# 24V_Load_Switches.net
KiCad netlist of a schematic drawn in Altium Designer
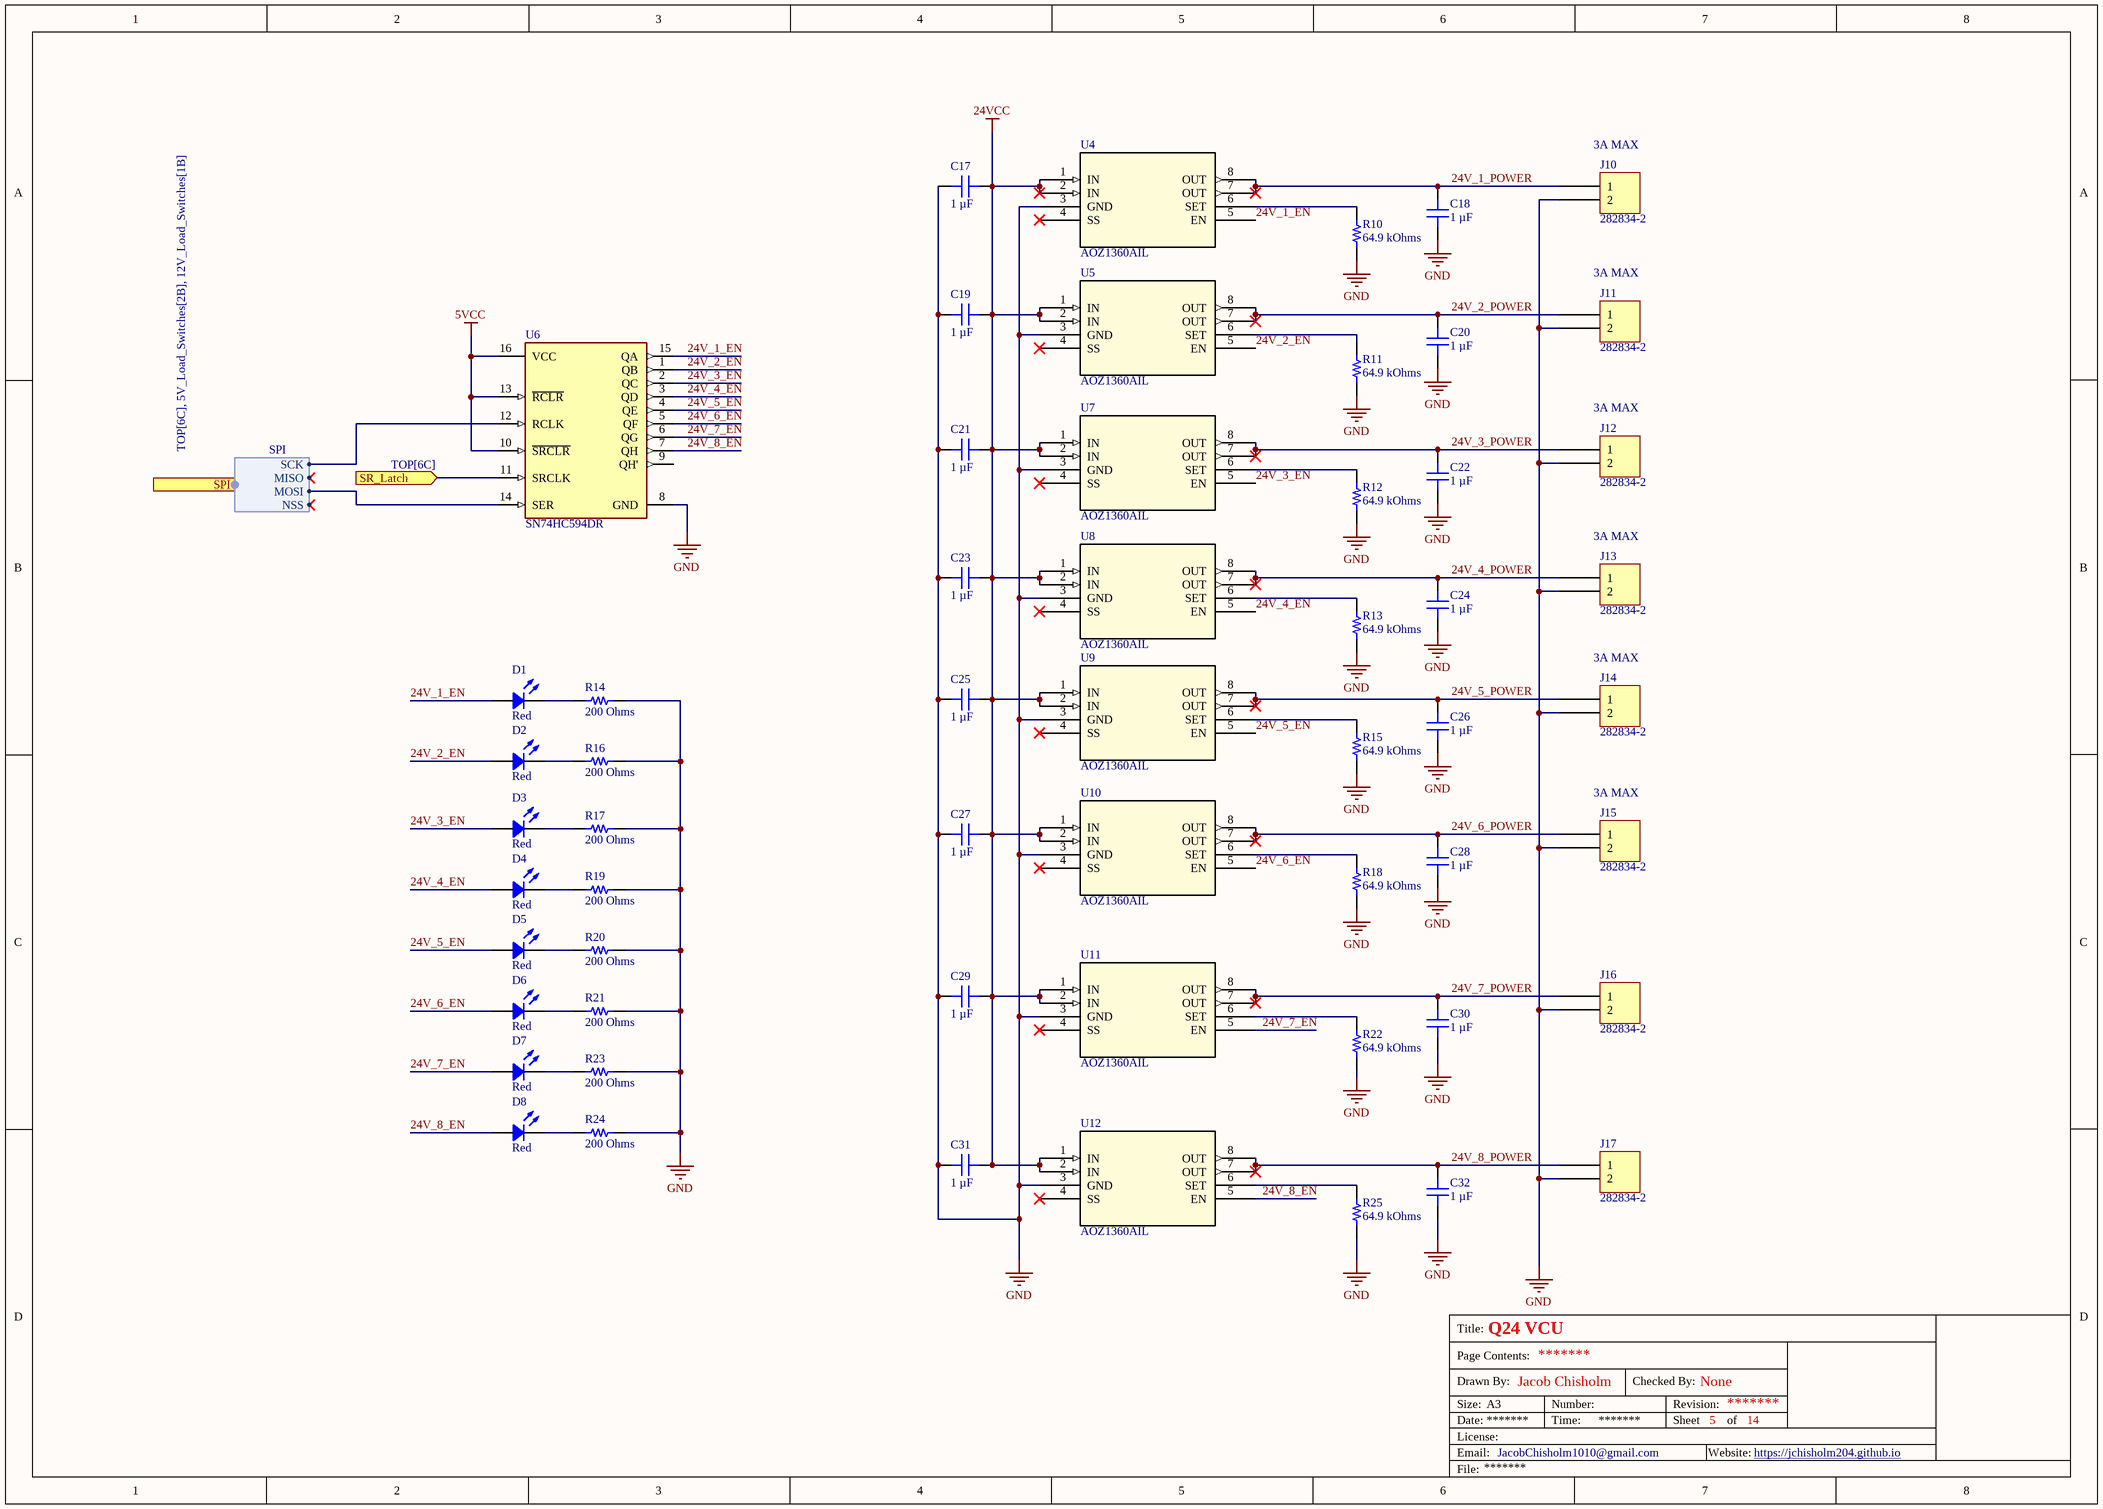
[diagram p0: 24V_Load_Switches.SchDoc]

(export (version "E")
  (design (tool "Eeschema 10.0.6"))
  (components
    (comp (ref "C17")
      (value "1 µF")
      (footprint "CAP 0805_2012")
      (description "CAP CER 1UF 50V X7R 0805")
      (fields
        (field (name "PART NUMBER") "GCJ21BR71H105KA01L")
        (field (name "MANUFACTURER") "Murata Electronics")
      )
      (libsource (lib "altium_library") (part "Capacitor"))
    )
    (comp (ref "C18")
      (value "1 µF")
      (footprint "CAP 0805_2012")
      (description "CAP CER 1UF 50V X7R 0805")
      (fields
        (field (name "PART NUMBER") "GCJ21BR71H105KA01L")
        (field (name "MANUFACTURER") "Murata Electronics")
      )
      (libsource (lib "altium_library") (part "Capacitor"))
    )
    (comp (ref "C19")
      (value "1 µF")
      (footprint "CAP 0805_2012")
      (description "CAP CER 1UF 50V X7R 0805")
      (fields
        (field (name "PART NUMBER") "GCJ21BR71H105KA01L")
        (field (name "MANUFACTURER") "Murata Electronics")
      )
      (libsource (lib "altium_library") (part "Capacitor"))
    )
    (comp (ref "C20")
      (value "1 µF")
      (footprint "CAP 0805_2012")
      (description "CAP CER 1UF 50V X7R 0805")
      (fields
        (field (name "PART NUMBER") "GCJ21BR71H105KA01L")
        (field (name "MANUFACTURER") "Murata Electronics")
      )
      (libsource (lib "altium_library") (part "Capacitor"))
    )
    (comp (ref "C21")
      (value "1 µF")
      (footprint "CAP 0805_2012")
      (description "CAP CER 1UF 50V X7R 0805")
      (fields
        (field (name "PART NUMBER") "GCJ21BR71H105KA01L")
        (field (name "MANUFACTURER") "Murata Electronics")
      )
      (libsource (lib "altium_library") (part "Capacitor"))
    )
    (comp (ref "C22")
      (value "1 µF")
      (footprint "CAP 0805_2012")
      (description "CAP CER 1UF 50V X7R 0805")
      (fields
        (field (name "PART NUMBER") "GCJ21BR71H105KA01L")
        (field (name "MANUFACTURER") "Murata Electronics")
      )
      (libsource (lib "altium_library") (part "Capacitor"))
    )
    (comp (ref "C23")
      (value "1 µF")
      (footprint "CAP 0805_2012")
      (description "CAP CER 1UF 50V X7R 0805")
      (fields
        (field (name "PART NUMBER") "GCJ21BR71H105KA01L")
        (field (name "MANUFACTURER") "Murata Electronics")
      )
      (libsource (lib "altium_library") (part "Capacitor"))
    )
    (comp (ref "C24")
      (value "1 µF")
      (footprint "CAP 0805_2012")
      (description "CAP CER 1UF 50V X7R 0805")
      (fields
        (field (name "PART NUMBER") "GCJ21BR71H105KA01L")
        (field (name "MANUFACTURER") "Murata Electronics")
      )
      (libsource (lib "altium_library") (part "Capacitor"))
    )
    (comp (ref "C25")
      (value "1 µF")
      (footprint "CAP 0805_2012")
      (description "CAP CER 1UF 50V X7R 0805")
      (fields
        (field (name "PART NUMBER") "GCJ21BR71H105KA01L")
        (field (name "MANUFACTURER") "Murata Electronics")
      )
      (libsource (lib "altium_library") (part "Capacitor"))
    )
    (comp (ref "C26")
      (value "1 µF")
      (footprint "CAP 0805_2012")
      (description "CAP CER 1UF 50V X7R 0805")
      (fields
        (field (name "PART NUMBER") "GCJ21BR71H105KA01L")
        (field (name "MANUFACTURER") "Murata Electronics")
      )
      (libsource (lib "altium_library") (part "Capacitor"))
    )
    (comp (ref "C27")
      (value "1 µF")
      (footprint "CAP 0805_2012")
      (description "CAP CER 1UF 50V X7R 0805")
      (fields
        (field (name "PART NUMBER") "GCJ21BR71H105KA01L")
        (field (name "MANUFACTURER") "Murata Electronics")
      )
      (libsource (lib "altium_library") (part "Capacitor"))
    )
    (comp (ref "C28")
      (value "1 µF")
      (footprint "CAP 0805_2012")
      (description "CAP CER 1UF 50V X7R 0805")
      (fields
        (field (name "PART NUMBER") "GCJ21BR71H105KA01L")
        (field (name "MANUFACTURER") "Murata Electronics")
      )
      (libsource (lib "altium_library") (part "Capacitor"))
    )
    (comp (ref "C29")
      (value "1 µF")
      (footprint "CAP 0805_2012")
      (description "0805 X7S 1UF10% 100V")
      (fields (field (name "PART NUMBER") "08051Z105KAT2A") (field (name "MANUFACTURER") "KYOCERA AVX"))
      (libsource (lib "Celestial Altium Library - altium_library") (part "Capacitor"))
    )
    (comp (ref "C30")
      (value "1 µF")
      (footprint "CAP 0805_2012")
      (description "0805 X7S 1UF10% 100V")
      (fields (field (name "PART NUMBER") "08051Z105KAT2A") (field (name "MANUFACTURER") "KYOCERA AVX"))
      (libsource (lib "Celestial Altium Library - altium_library") (part "Capacitor"))
    )
    (comp (ref "C31")
      (value "1 µF")
      (footprint "CAP 0805_2012")
      (description "0805 X7S 1UF10% 100V")
      (fields (field (name "PART NUMBER") "08051Z105KAT2A") (field (name "MANUFACTURER") "KYOCERA AVX"))
      (libsource (lib "Celestial Altium Library - altium_library") (part "Capacitor"))
    )
    (comp (ref "C32")
      (value "1 µF")
      (footprint "CAP 0805_2012")
      (description "0805 X7S 1UF10% 100V")
      (fields (field (name "PART NUMBER") "08051Z105KAT2A") (field (name "MANUFACTURER") "KYOCERA AVX"))
      (libsource (lib "Celestial Altium Library - altium_library") (part "Capacitor"))
    )
    (comp (ref "D1")
      (value "Red")
      (footprint "LED 0603_1608 RED")
      (description "LED RED CLEAR 2SMD")
      (fields
        (field (name "PART NUMBER") "19-213SDRC/S259/TR8")
        (field (name "MANUFACTURER") "Everlight Electronics Co Ltd")
      )
      (libsource (lib "Celestial Altium Library - altium_library") (part "LED"))
    )
    (comp (ref "D2")
      (value "Red")
      (footprint "LED 0603_1608 RED")
      (description "LED RED CLEAR 2SMD")
      (fields
        (field (name "PART NUMBER") "19-213SDRC/S259/TR8")
        (field (name "MANUFACTURER") "Everlight Electronics Co Ltd")
      )
      (libsource (lib "Celestial Altium Library - altium_library") (part "LED"))
    )
    (comp (ref "D3")
      (value "Red")
      (footprint "LED 0603_1608 RED")
      (description "LED RED CLEAR 2SMD")
      (fields
        (field (name "PART NUMBER") "19-213SDRC/S259/TR8")
        (field (name "MANUFACTURER") "Everlight Electronics Co Ltd")
      )
      (libsource (lib "Celestial Altium Library - altium_library") (part "LED"))
    )
    (comp (ref "D4")
      (value "Red")
      (footprint "LED 0603_1608 RED")
      (description "LED RED CLEAR 2SMD")
      (fields
        (field (name "PART NUMBER") "19-213SDRC/S259/TR8")
        (field (name "MANUFACTURER") "Everlight Electronics Co Ltd")
      )
      (libsource (lib "Celestial Altium Library - altium_library") (part "LED"))
    )
    (comp (ref "D5")
      (value "Red")
      (footprint "LED 0603_1608 RED")
      (description "LED RED CLEAR 2SMD")
      (fields
        (field (name "PART NUMBER") "19-213SDRC/S259/TR8")
        (field (name "MANUFACTURER") "Everlight Electronics Co Ltd")
      )
      (libsource (lib "Celestial Altium Library - altium_library") (part "LED"))
    )
    (comp (ref "D6")
      (value "Red")
      (footprint "LED 0603_1608 RED")
      (description "LED RED CLEAR 2SMD")
      (fields
        (field (name "PART NUMBER") "19-213SDRC/S259/TR8")
        (field (name "MANUFACTURER") "Everlight Electronics Co Ltd")
      )
      (libsource (lib "Celestial Altium Library - altium_library") (part "LED"))
    )
    (comp (ref "D7")
      (value "Red")
      (footprint "LED 0603_1608 RED")
      (description "LED RED CLEAR 2SMD")
      (fields
        (field (name "PART NUMBER") "19-213SDRC/S259/TR8")
        (field (name "MANUFACTURER") "Everlight Electronics Co Ltd")
      )
      (libsource (lib "Celestial Altium Library - altium_library") (part "LED"))
    )
    (comp (ref "D8")
      (value "Red")
      (footprint "LED 0603_1608 RED")
      (description "LED RED CLEAR 2SMD")
      (fields
        (field (name "PART NUMBER") "19-213SDRC/S259/TR8")
        (field (name "MANUFACTURER") "Everlight Electronics Co Ltd")
      )
      (libsource (lib "Celestial Altium Library - altium_library") (part "LED"))
    )
    (comp (ref "J10")
      (value "282834-2")
      (footprint "TE 282834-2")
      (description "TERM BLK 2P SIDE ENT 2.54MM PCB")
      (fields (field (name "MANUFACTURER") "TE Connectivity AMP Connectors") (field (name "VOLTAGE") "150V"))
      (libsource (lib "altium_library") (part "2 Pin"))
    )
    (comp (ref "J11")
      (value "282834-2")
      (footprint "TE 282834-2")
      (description "TERM BLK 2P SIDE ENT 2.54MM PCB")
      (fields (field (name "MANUFACTURER") "TE Connectivity AMP Connectors") (field (name "VOLTAGE") "150V"))
      (libsource (lib "altium_library") (part "2 Pin"))
    )
    (comp (ref "J12")
      (value "282834-2")
      (footprint "TE 282834-2")
      (description "TERM BLK 2P SIDE ENT 2.54MM PCB")
      (fields (field (name "MANUFACTURER") "TE Connectivity AMP Connectors") (field (name "VOLTAGE") "150V"))
      (libsource (lib "altium_library") (part "2 Pin"))
    )
    (comp (ref "J13")
      (value "282834-2")
      (footprint "TE 282834-2")
      (description "TERM BLK 2P SIDE ENT 2.54MM PCB")
      (fields (field (name "MANUFACTURER") "TE Connectivity AMP Connectors") (field (name "VOLTAGE") "150V"))
      (libsource (lib "altium_library") (part "2 Pin"))
    )
    (comp (ref "J14")
      (value "282834-2")
      (footprint "TE 282834-2")
      (description "TERM BLK 2P SIDE ENT 2.54MM PCB")
      (fields (field (name "MANUFACTURER") "TE Connectivity AMP Connectors") (field (name "VOLTAGE") "150V"))
      (libsource (lib "altium_library") (part "2 Pin"))
    )
    (comp (ref "J15")
      (value "282834-2")
      (footprint "TE 282834-2")
      (description "TERM BLK 2P SIDE ENT 2.54MM PCB")
      (fields (field (name "MANUFACTURER") "TE Connectivity AMP Connectors") (field (name "VOLTAGE") "150V"))
      (libsource (lib "altium_library") (part "2 Pin"))
    )
    (comp (ref "J16")
      (value "282834-2")
      (footprint "TE 282834-2")
      (description "TERM BLK 2P SIDE ENT 2.54MM PCB")
      (fields (field (name "MANUFACTURER") "TE Connectivity AMP Connectors") (field (name "VOLTAGE") "150V"))
      (libsource (lib "Celestial Altium Library - altium_library") (part "2 Pin"))
    )
    (comp (ref "J17")
      (value "282834-2")
      (footprint "TE 282834-2")
      (description "TERM BLK 2P SIDE ENT 2.54MM PCB")
      (fields (field (name "MANUFACTURER") "TE Connectivity AMP Connectors") (field (name "VOLTAGE") "150V"))
      (libsource (lib "Celestial Altium Library - altium_library") (part "2 Pin"))
    )
    (comp (ref "R10")
      (value "64.9 kOhms")
      (footprint "RES 0603_1608")
      (description "RES SMD 64.9K OHM 0.1% 1/6W 0603")
      (fields
        (field (name "PART NUMBER") "7-2176089-3")
        (field (name "MANUFACTURER") "TE Connectivity Passive Product")
      )
      (libsource (lib "altium_library") (part "Resistor"))
    )
    (comp (ref "R11")
      (value "64.9 kOhms")
      (footprint "RES 0603_1608")
      (description "RES SMD 64.9K OHM 0.1% 1/6W 0603")
      (fields
        (field (name "PART NUMBER") "7-2176089-3")
        (field (name "MANUFACTURER") "TE Connectivity Passive Product")
      )
      (libsource (lib "altium_library") (part "Resistor"))
    )
    (comp (ref "R12")
      (value "64.9 kOhms")
      (footprint "RES 0603_1608")
      (description "RES SMD 64.9K OHM 0.1% 1/6W 0603")
      (fields
        (field (name "PART NUMBER") "7-2176089-3")
        (field (name "MANUFACTURER") "TE Connectivity Passive Product")
      )
      (libsource (lib "altium_library") (part "Resistor"))
    )
    (comp (ref "R13")
      (value "64.9 kOhms")
      (footprint "RES 0603_1608")
      (description "RES SMD 64.9K OHM 0.1% 1/6W 0603")
      (fields
        (field (name "PART NUMBER") "7-2176089-3")
        (field (name "MANUFACTURER") "TE Connectivity Passive Product")
      )
      (libsource (lib "altium_library") (part "Resistor"))
    )
    (comp (ref "R14")
      (value "200 Ohms")
      (footprint "RES 0603_1608")
      (description "RES 200 OHM 0.1% 1/5W 0603")
      (fields
        (field (name "PART NUMBER") "RS73F1JTTD2000B")
        (field (name "MANUFACTURER") "KOA Speer Electronics, Inc.")
      )
      (libsource (lib "Celestial Altium Library - altium_library") (part "Resistor"))
    )
    (comp (ref "R15")
      (value "64.9 kOhms")
      (footprint "RES 0603_1608")
      (description "RES SMD 64.9K OHM 0.1% 1/6W 0603")
      (fields
        (field (name "PART NUMBER") "7-2176089-3")
        (field (name "MANUFACTURER") "TE Connectivity Passive Product")
      )
      (libsource (lib "altium_library") (part "Resistor"))
    )
    (comp (ref "R16")
      (value "200 Ohms")
      (footprint "RES 0603_1608")
      (description "RES 200 OHM 0.1% 1/5W 0603")
      (fields
        (field (name "PART NUMBER") "RS73F1JTTD2000B")
        (field (name "MANUFACTURER") "KOA Speer Electronics, Inc.")
      )
      (libsource (lib "Celestial Altium Library - altium_library") (part "Resistor"))
    )
    (comp (ref "R17")
      (value "200 Ohms")
      (footprint "RES 0603_1608")
      (description "RES 200 OHM 0.1% 1/5W 0603")
      (fields
        (field (name "PART NUMBER") "RS73F1JTTD2000B")
        (field (name "MANUFACTURER") "KOA Speer Electronics, Inc.")
      )
      (libsource (lib "Celestial Altium Library - altium_library") (part "Resistor"))
    )
    (comp (ref "R18")
      (value "64.9 kOhms")
      (footprint "RES 0603_1608")
      (description "RES SMD 64.9K OHM 0.1% 1/6W 0603")
      (fields
        (field (name "PART NUMBER") "7-2176089-3")
        (field (name "MANUFACTURER") "TE Connectivity Passive Product")
      )
      (libsource (lib "altium_library") (part "Resistor"))
    )
    (comp (ref "R19")
      (value "200 Ohms")
      (footprint "RES 0603_1608")
      (description "RES 200 OHM 0.1% 1/5W 0603")
      (fields
        (field (name "PART NUMBER") "RS73F1JTTD2000B")
        (field (name "MANUFACTURER") "KOA Speer Electronics, Inc.")
      )
      (libsource (lib "Celestial Altium Library - altium_library") (part "Resistor"))
    )
    (comp (ref "R20")
      (value "200 Ohms")
      (footprint "RES 0603_1608")
      (description "RES 200 OHM 0.1% 1/5W 0603")
      (fields
        (field (name "PART NUMBER") "RS73F1JTTD2000B")
        (field (name "MANUFACTURER") "KOA Speer Electronics, Inc.")
      )
      (libsource (lib "Celestial Altium Library - altium_library") (part "Resistor"))
    )
    (comp (ref "R21")
      (value "200 Ohms")
      (footprint "RES 0603_1608")
      (description "RES 200 OHM 0.1% 1/5W 0603")
      (fields
        (field (name "PART NUMBER") "RS73F1JTTD2000B")
        (field (name "MANUFACTURER") "KOA Speer Electronics, Inc.")
      )
      (libsource (lib "Celestial Altium Library - altium_library") (part "Resistor"))
    )
    (comp (ref "R22")
      (value "64.9 kOhms")
      (footprint "RES 0603_1608")
      (description "RES 64.9K OHM 0.1% 0.15W 0603")
      (fields
        (field (name "PART NUMBER") "PTN0603E6492BST1")
        (field (name "MANUFACTURER") "Vishay Thin Film")
      )
      (libsource (lib "Celestial Altium Library - altium_library") (part "Resistor"))
    )
    (comp (ref "R23")
      (value "200 Ohms")
      (footprint "RES 0603_1608")
      (description "RES 200 OHM 0.1% 1/5W 0603")
      (fields
        (field (name "PART NUMBER") "RS73F1JTTD2000B")
        (field (name "MANUFACTURER") "KOA Speer Electronics, Inc.")
      )
      (libsource (lib "Celestial Altium Library - altium_library") (part "Resistor"))
    )
    (comp (ref "R24")
      (value "200 Ohms")
      (footprint "RES 0603_1608")
      (description "RES 200 OHM 0.1% 1/5W 0603")
      (fields
        (field (name "PART NUMBER") "RS73F1JTTD2000B")
        (field (name "MANUFACTURER") "KOA Speer Electronics, Inc.")
      )
      (libsource (lib "Celestial Altium Library - altium_library") (part "Resistor"))
    )
    (comp (ref "R25")
      (value "64.9 kOhms")
      (footprint "RES 0603_1608")
      (description "RES 64.9K OHM 0.1% 0.15W 0603")
      (fields
        (field (name "PART NUMBER") "PTN0603E6492BST1")
        (field (name "MANUFACTURER") "Vishay Thin Film")
      )
      (libsource (lib "Celestial Altium Library - altium_library") (part "Resistor"))
    )
    (comp (ref "U4")
      (value "AOZ1360AIL")
      (footprint "AOZ1360AIL_AOS")
      (description "No Description Available")
      (fields (field (name "COPYRIGHT") "Copyright (C) 2023 Ultra Librarian. All rights reserved."))
      (libsource (lib "AOZ1360AIL") (part "AOZ1360AIL"))
    )
    (comp (ref "U5")
      (value "AOZ1360AIL")
      (footprint "AOZ1360AIL_AOS")
      (description "No Description Available")
      (fields (field (name "COPYRIGHT") "Copyright (C) 2023 Ultra Librarian. All rights reserved."))
      (libsource (lib "AOZ1360AIL") (part "AOZ1360AIL"))
    )
    (comp (ref "U6")
      (value "SN74HC594DR")
      (footprint "FP-D0016A-IPC_A")
      (description "IC SHIFT REGISTER 8BIT 16-SOIC")
      (libsource (lib "Altium Content Vault") (part "6ffdf0eb1487316571b39b71ede2db7"))
    )
    (comp (ref "U7")
      (value "AOZ1360AIL")
      (footprint "AOZ1360AIL_AOS")
      (description "No Description Available")
      (fields (field (name "COPYRIGHT") "Copyright (C) 2023 Ultra Librarian. All rights reserved."))
      (libsource (lib "AOZ1360AIL") (part "AOZ1360AIL"))
    )
    (comp (ref "U8")
      (value "AOZ1360AIL")
      (footprint "AOZ1360AIL_AOS")
      (description "No Description Available")
      (fields (field (name "COPYRIGHT") "Copyright (C) 2023 Ultra Librarian. All rights reserved."))
      (libsource (lib "AOZ1360AIL") (part "AOZ1360AIL"))
    )
    (comp (ref "U9")
      (value "AOZ1360AIL")
      (footprint "AOZ1360AIL_AOS")
      (description "No Description Available")
      (fields (field (name "COPYRIGHT") "Copyright (C) 2023 Ultra Librarian. All rights reserved."))
      (libsource (lib "AOZ1360AIL") (part "AOZ1360AIL"))
    )
    (comp (ref "U10")
      (value "AOZ1360AIL")
      (footprint "AOZ1360AIL_AOS")
      (description "No Description Available")
      (fields (field (name "COPYRIGHT") "Copyright (C) 2023 Ultra Librarian. All rights reserved."))
      (libsource (lib "AOZ1360AIL") (part "AOZ1360AIL"))
    )
    (comp (ref "U11")
      (value "AOZ1360AIL")
      (footprint "AOZ1360AIL_AOS")
      (description "No Description Available")
      (fields (field (name "COPYRIGHT") "Copyright (C) 2024 Ultra Librarian. All rights reserved."))
      (libsource (lib "AOZ1360AIL") (part "AOZ1360AIL"))
    )
    (comp (ref "U12")
      (value "AOZ1360AIL")
      (footprint "AOZ1360AIL_AOS")
      (description "No Description Available")
      (fields (field (name "COPYRIGHT") "Copyright (C) 2024 Ultra Librarian. All rights reserved."))
      (libsource (lib "AOZ1360AIL") (part "AOZ1360AIL"))
    )
  )
  (nets
    (net (code "2") (name "/24V_1_EN") (class "Default")
      (node (ref "D1") (pin "1") (pinfunction "1_1") (pintype "passive"))
      (node (ref "U4") (pin "5") (pinfunction "EN_5") (pintype "passive"))
      (node (ref "U6") (pin "15") (pinfunction "QA_15") (pintype "output"))
    )
    (net (code "3") (name "/24V_1_POWER") (class "Default")
      (node (ref "C18") (pin "2") (pinfunction "2_2") (pintype "passive"))
      (node (ref "J10") (pin "1") (pinfunction "1_1") (pintype "passive"))
      (node (ref "U4") (pin "7") (pinfunction "OUT_7") (pintype "output"))
      (node (ref "U4") (pin "8") (pinfunction "OUT_8") (pintype "output"))
    )
    (net (code "4") (name "/24V_2_EN") (class "Default")
      (node (ref "D2") (pin "1") (pinfunction "1_1") (pintype "passive"))
      (node (ref "U5") (pin "5") (pinfunction "EN_5") (pintype "passive"))
      (node (ref "U6") (pin "1") (pinfunction "QB_1") (pintype "output"))
    )
    (net (code "5") (name "/24V_2_POWER") (class "Default")
      (node (ref "C20") (pin "2") (pinfunction "2_2") (pintype "passive"))
      (node (ref "J11") (pin "1") (pinfunction "1_1") (pintype "passive"))
      (node (ref "U5") (pin "7") (pinfunction "OUT_7") (pintype "output"))
      (node (ref "U5") (pin "8") (pinfunction "OUT_8") (pintype "output"))
    )
    (net (code "6") (name "/24V_3_EN") (class "Default")
      (node (ref "D3") (pin "1") (pinfunction "1_1") (pintype "passive"))
      (node (ref "U6") (pin "2") (pinfunction "QC_2") (pintype "output"))
      (node (ref "U7") (pin "5") (pinfunction "EN_5") (pintype "passive"))
    )
    (net (code "7") (name "/24V_3_POWER") (class "Default")
      (node (ref "C22") (pin "2") (pinfunction "2_2") (pintype "passive"))
      (node (ref "J12") (pin "1") (pinfunction "1_1") (pintype "passive"))
      (node (ref "U7") (pin "7") (pinfunction "OUT_7") (pintype "output"))
      (node (ref "U7") (pin "8") (pinfunction "OUT_8") (pintype "output"))
    )
    (net (code "8") (name "/24V_4_EN") (class "Default")
      (node (ref "D4") (pin "1") (pinfunction "1_1") (pintype "passive"))
      (node (ref "U6") (pin "3") (pinfunction "QD_3") (pintype "output"))
      (node (ref "U8") (pin "5") (pinfunction "EN_5") (pintype "passive"))
    )
    (net (code "9") (name "/24V_4_POWER") (class "Default")
      (node (ref "C24") (pin "2") (pinfunction "2_2") (pintype "passive"))
      (node (ref "J13") (pin "1") (pinfunction "1_1") (pintype "passive"))
      (node (ref "U8") (pin "7") (pinfunction "OUT_7") (pintype "output"))
      (node (ref "U8") (pin "8") (pinfunction "OUT_8") (pintype "output"))
    )
    (net (code "10") (name "/24V_5_EN") (class "Default")
      (node (ref "D5") (pin "1") (pinfunction "1_1") (pintype "passive"))
      (node (ref "U6") (pin "4") (pinfunction "QE_4") (pintype "output"))
      (node (ref "U9") (pin "5") (pinfunction "EN_5") (pintype "passive"))
    )
    (net (code "11") (name "/24V_5_POWER") (class "Default")
      (node (ref "C26") (pin "2") (pinfunction "2_2") (pintype "passive"))
      (node (ref "J14") (pin "1") (pinfunction "1_1") (pintype "passive"))
      (node (ref "U9") (pin "7") (pinfunction "OUT_7") (pintype "output"))
      (node (ref "U9") (pin "8") (pinfunction "OUT_8") (pintype "output"))
    )
    (net (code "12") (name "/24V_6_EN") (class "Default")
      (node (ref "D6") (pin "1") (pinfunction "1_1") (pintype "passive"))
      (node (ref "U10") (pin "5") (pinfunction "EN_5") (pintype "passive"))
      (node (ref "U6") (pin "5") (pinfunction "QF_5") (pintype "output"))
    )
    (net (code "13") (name "/24V_6_POWER") (class "Default")
      (node (ref "C28") (pin "2") (pinfunction "2_2") (pintype "passive"))
      (node (ref "J15") (pin "1") (pinfunction "1_1") (pintype "passive"))
      (node (ref "U10") (pin "7") (pinfunction "OUT_7") (pintype "output"))
      (node (ref "U10") (pin "8") (pinfunction "OUT_8") (pintype "output"))
    )
    (net (code "14") (name "/24V_7_EN") (class "Default")
      (node (ref "D7") (pin "1") (pinfunction "1_1") (pintype "passive"))
      (node (ref "U11") (pin "5") (pinfunction "EN_5") (pintype "passive"))
      (node (ref "U6") (pin "6") (pinfunction "QG_6") (pintype "output"))
    )
    (net (code "15") (name "/24V_7_POWER") (class "Default")
      (node (ref "C30") (pin "2") (pinfunction "2_2") (pintype "passive"))
      (node (ref "J16") (pin "1") (pinfunction "1_1") (pintype "passive"))
      (node (ref "U11") (pin "7") (pinfunction "OUT_7") (pintype "output"))
      (node (ref "U11") (pin "8") (pinfunction "OUT_8") (pintype "output"))
    )
    (net (code "16") (name "/24V_8_EN") (class "Default")
      (node (ref "D8") (pin "1") (pinfunction "1_1") (pintype "passive"))
      (node (ref "U12") (pin "5") (pinfunction "EN_5") (pintype "passive"))
      (node (ref "U6") (pin "7") (pinfunction "QH_7") (pintype "output"))
    )
    (net (code "17") (name "/24V_8_POWER") (class "Default")
      (node (ref "C32") (pin "2") (pinfunction "2_2") (pintype "passive"))
      (node (ref "J17") (pin "1") (pinfunction "1_1") (pintype "passive"))
      (node (ref "U12") (pin "7") (pinfunction "OUT_7") (pintype "output"))
      (node (ref "U12") (pin "8") (pinfunction "OUT_8") (pintype "output"))
    )
    (net (code "18") (name "/MOSI") (class "Default")
      (node (ref "U6") (pin "14") (pinfunction "SER_14") (pintype "input"))
    )
    (net (code "19") (name "/SCK") (class "Default")
      (node (ref "U6") (pin "12") (pinfunction "RCLK_12") (pintype "input"))
    )
    (net (code "20") (name "/SR_Latch") (class "Default")
      (node (ref "U6") (pin "11") (pinfunction "SRCLK_11") (pintype "input"))
    )
    (net (code "22") (name "5VCC") (class "Default")
      (node (ref "U6") (pin "10") (pinfunction "~{SRCLR}_10") (pintype "input"))
      (node (ref "U6") (pin "13") (pinfunction "~{RCLR}_13") (pintype "input"))
      (node (ref "U6") (pin "16") (pinfunction "VCC_16") (pintype "power_in"))
    )
    (net (code "23") (name "24VCC") (class "Default")
      (node (ref "C17") (pin "1") (pinfunction "1_1") (pintype "passive"))
      (node (ref "C19") (pin "1") (pinfunction "1_1") (pintype "passive"))
      (node (ref "C21") (pin "1") (pinfunction "1_1") (pintype "passive"))
      (node (ref "C23") (pin "1") (pinfunction "1_1") (pintype "passive"))
      (node (ref "C25") (pin "1") (pinfunction "1_1") (pintype "passive"))
      (node (ref "C27") (pin "1") (pinfunction "1_1") (pintype "passive"))
      (node (ref "C29") (pin "2") (pinfunction "2_2") (pintype "passive"))
      (node (ref "C31") (pin "2") (pinfunction "2_2") (pintype "passive"))
      (node (ref "U10") (pin "1") (pinfunction "IN_1") (pintype "input"))
      (node (ref "U10") (pin "2") (pinfunction "IN_2") (pintype "input"))
      (node (ref "U11") (pin "1") (pinfunction "IN_1") (pintype "input"))
      (node (ref "U11") (pin "2") (pinfunction "IN_2") (pintype "input"))
      (node (ref "U12") (pin "1") (pinfunction "IN_1") (pintype "input"))
      (node (ref "U12") (pin "2") (pinfunction "IN_2") (pintype "input"))
      (node (ref "U4") (pin "1") (pinfunction "IN_1") (pintype "input"))
      (node (ref "U4") (pin "2") (pinfunction "IN_2") (pintype "input"))
      (node (ref "U5") (pin "1") (pinfunction "IN_1") (pintype "input"))
      (node (ref "U5") (pin "2") (pinfunction "IN_2") (pintype "input"))
      (node (ref "U7") (pin "1") (pinfunction "IN_1") (pintype "input"))
      (node (ref "U7") (pin "2") (pinfunction "IN_2") (pintype "input"))
      (node (ref "U8") (pin "1") (pinfunction "IN_1") (pintype "input"))
      (node (ref "U8") (pin "2") (pinfunction "IN_2") (pintype "input"))
      (node (ref "U9") (pin "1") (pinfunction "IN_1") (pintype "input"))
      (node (ref "U9") (pin "2") (pinfunction "IN_2") (pintype "input"))
    )
    (net (code "24") (name "GND") (class "Default")
      (node (ref "C17") (pin "2") (pinfunction "2_2") (pintype "passive"))
      (node (ref "C18") (pin "1") (pinfunction "1_1") (pintype "passive"))
      (node (ref "C19") (pin "2") (pinfunction "2_2") (pintype "passive"))
      (node (ref "C20") (pin "1") (pinfunction "1_1") (pintype "passive"))
      (node (ref "C21") (pin "2") (pinfunction "2_2") (pintype "passive"))
      (node (ref "C22") (pin "1") (pinfunction "1_1") (pintype "passive"))
      (node (ref "C23") (pin "2") (pinfunction "2_2") (pintype "passive"))
      (node (ref "C24") (pin "1") (pinfunction "1_1") (pintype "passive"))
      (node (ref "C25") (pin "2") (pinfunction "2_2") (pintype "passive"))
      (node (ref "C26") (pin "1") (pinfunction "1_1") (pintype "passive"))
      (node (ref "C27") (pin "2") (pinfunction "2_2") (pintype "passive"))
      (node (ref "C28") (pin "1") (pinfunction "1_1") (pintype "passive"))
      (node (ref "C29") (pin "1") (pinfunction "1_1") (pintype "passive"))
      (node (ref "C30") (pin "1") (pinfunction "1_1") (pintype "passive"))
      (node (ref "C31") (pin "1") (pinfunction "1_1") (pintype "passive"))
      (node (ref "C32") (pin "1") (pinfunction "1_1") (pintype "passive"))
      (node (ref "J10") (pin "2") (pinfunction "2_2") (pintype "passive"))
      (node (ref "J11") (pin "2") (pinfunction "2_2") (pintype "passive"))
      (node (ref "J12") (pin "2") (pinfunction "2_2") (pintype "passive"))
      (node (ref "J13") (pin "2") (pinfunction "2_2") (pintype "passive"))
      (node (ref "J14") (pin "2") (pinfunction "2_2") (pintype "passive"))
      (node (ref "J15") (pin "2") (pinfunction "2_2") (pintype "passive"))
      (node (ref "J16") (pin "2") (pinfunction "2_2") (pintype "passive"))
      (node (ref "J17") (pin "2") (pinfunction "2_2") (pintype "passive"))
      (node (ref "R10") (pin "1") (pinfunction "1_1") (pintype "passive"))
      (node (ref "R11") (pin "1") (pinfunction "1_1") (pintype "passive"))
      (node (ref "R12") (pin "1") (pinfunction "1_1") (pintype "passive"))
      (node (ref "R13") (pin "1") (pinfunction "1_1") (pintype "passive"))
      (node (ref "R14") (pin "2") (pinfunction "2_2") (pintype "passive"))
      (node (ref "R15") (pin "1") (pinfunction "1_1") (pintype "passive"))
      (node (ref "R16") (pin "2") (pinfunction "2_2") (pintype "passive"))
      (node (ref "R17") (pin "2") (pinfunction "2_2") (pintype "passive"))
      (node (ref "R18") (pin "1") (pinfunction "1_1") (pintype "passive"))
      (node (ref "R19") (pin "2") (pinfunction "2_2") (pintype "passive"))
      (node (ref "R20") (pin "2") (pinfunction "2_2") (pintype "passive"))
      (node (ref "R21") (pin "2") (pinfunction "2_2") (pintype "passive"))
      (node (ref "R22") (pin "1") (pinfunction "1_1") (pintype "passive"))
      (node (ref "R23") (pin "2") (pinfunction "2_2") (pintype "passive"))
      (node (ref "R24") (pin "2") (pinfunction "2_2") (pintype "passive"))
      (node (ref "R25") (pin "1") (pinfunction "1_1") (pintype "passive"))
      (node (ref "U10") (pin "3") (pinfunction "GND_3") (pintype "power_in"))
      (node (ref "U11") (pin "3") (pinfunction "GND_3") (pintype "power_in"))
      (node (ref "U12") (pin "3") (pinfunction "GND_3") (pintype "power_in"))
      (node (ref "U4") (pin "3") (pinfunction "GND_3") (pintype "power_in"))
      (node (ref "U5") (pin "3") (pinfunction "GND_3") (pintype "power_in"))
      (node (ref "U6") (pin "8") (pinfunction "GND_8") (pintype "power_in"))
      (node (ref "U7") (pin "3") (pinfunction "GND_3") (pintype "power_in"))
      (node (ref "U8") (pin "3") (pinfunction "GND_3") (pintype "power_in"))
      (node (ref "U9") (pin "3") (pinfunction "GND_3") (pintype "power_in"))
    )
    (net (code "25") (name "Net-(D1-Pad2)") (class "Default")
      (node (ref "D1") (pin "2") (pinfunction "2_2") (pintype "passive"))
      (node (ref "R14") (pin "1") (pinfunction "1_1") (pintype "passive"))
    )
    (net (code "26") (name "Net-(D2-Pad2)") (class "Default")
      (node (ref "D2") (pin "2") (pinfunction "2_2") (pintype "passive"))
      (node (ref "R16") (pin "1") (pinfunction "1_1") (pintype "passive"))
    )
    (net (code "27") (name "Net-(D3-Pad2)") (class "Default")
      (node (ref "D3") (pin "2") (pinfunction "2_2") (pintype "passive"))
      (node (ref "R17") (pin "1") (pinfunction "1_1") (pintype "passive"))
    )
    (net (code "28") (name "Net-(D4-Pad2)") (class "Default")
      (node (ref "D4") (pin "2") (pinfunction "2_2") (pintype "passive"))
      (node (ref "R19") (pin "1") (pinfunction "1_1") (pintype "passive"))
    )
    (net (code "29") (name "Net-(D5-Pad2)") (class "Default")
      (node (ref "D5") (pin "2") (pinfunction "2_2") (pintype "passive"))
      (node (ref "R20") (pin "1") (pinfunction "1_1") (pintype "passive"))
    )
    (net (code "30") (name "Net-(D6-Pad2)") (class "Default")
      (node (ref "D6") (pin "2") (pinfunction "2_2") (pintype "passive"))
      (node (ref "R21") (pin "1") (pinfunction "1_1") (pintype "passive"))
    )
    (net (code "31") (name "Net-(D7-Pad2)") (class "Default")
      (node (ref "D7") (pin "2") (pinfunction "2_2") (pintype "passive"))
      (node (ref "R23") (pin "1") (pinfunction "1_1") (pintype "passive"))
    )
    (net (code "32") (name "Net-(D8-Pad2)") (class "Default")
      (node (ref "D8") (pin "2") (pinfunction "2_2") (pintype "passive"))
      (node (ref "R24") (pin "1") (pinfunction "1_1") (pintype "passive"))
    )
    (net (code "33") (name "Net-(U4-SET)") (class "Default")
      (node (ref "R10") (pin "2") (pinfunction "2_2") (pintype "passive"))
      (node (ref "U4") (pin "6") (pinfunction "SET_6") (pintype "passive"))
    )
    (net (code "34") (name "Net-(U5-SET)") (class "Default")
      (node (ref "R11") (pin "2") (pinfunction "2_2") (pintype "passive"))
      (node (ref "U5") (pin "6") (pinfunction "SET_6") (pintype "passive"))
    )
    (net (code "35") (name "Net-(U7-SET)") (class "Default")
      (node (ref "R12") (pin "2") (pinfunction "2_2") (pintype "passive"))
      (node (ref "U7") (pin "6") (pinfunction "SET_6") (pintype "passive"))
    )
    (net (code "36") (name "Net-(U8-SET)") (class "Default")
      (node (ref "R13") (pin "2") (pinfunction "2_2") (pintype "passive"))
      (node (ref "U8") (pin "6") (pinfunction "SET_6") (pintype "passive"))
    )
    (net (code "37") (name "Net-(U9-SET)") (class "Default")
      (node (ref "R15") (pin "2") (pinfunction "2_2") (pintype "passive"))
      (node (ref "U9") (pin "6") (pinfunction "SET_6") (pintype "passive"))
    )
    (net (code "38") (name "Net-(U10-SET)") (class "Default")
      (node (ref "R18") (pin "2") (pinfunction "2_2") (pintype "passive"))
      (node (ref "U10") (pin "6") (pinfunction "SET_6") (pintype "passive"))
    )
    (net (code "39") (name "Net-(U11-SET)") (class "Default")
      (node (ref "R22") (pin "2") (pinfunction "2_2") (pintype "passive"))
      (node (ref "U11") (pin "6") (pinfunction "SET_6") (pintype "passive"))
    )
    (net (code "40") (name "Net-(U12-SET)") (class "Default")
      (node (ref "R25") (pin "2") (pinfunction "2_2") (pintype "passive"))
      (node (ref "U12") (pin "6") (pinfunction "SET_6") (pintype "passive"))
    )
    (net (code "41") (name "unconnected-(U4-SS-Pad4)") (class "Default")
      (node (ref "U4") (pin "4") (pinfunction "SS_4") (pintype "passive+no_connect"))
    )
    (net (code "42") (name "unconnected-(U5-SS-Pad4)") (class "Default")
      (node (ref "U5") (pin "4") (pinfunction "SS_4") (pintype "passive+no_connect"))
    )
    (net (code "43") (name "unconnected-(U6-QH'-Pad9)") (class "Default")
      (node (ref "U6") (pin "9") (pinfunction "QH'_9") (pintype "output"))
    )
    (net (code "44") (name "unconnected-(U7-SS-Pad4)") (class "Default")
      (node (ref "U7") (pin "4") (pinfunction "SS_4") (pintype "passive+no_connect"))
    )
    (net (code "45") (name "unconnected-(U8-SS-Pad4)") (class "Default")
      (node (ref "U8") (pin "4") (pinfunction "SS_4") (pintype "passive+no_connect"))
    )
    (net (code "46") (name "unconnected-(U9-SS-Pad4)") (class "Default")
      (node (ref "U9") (pin "4") (pinfunction "SS_4") (pintype "passive+no_connect"))
    )
    (net (code "47") (name "unconnected-(U10-SS-Pad4)") (class "Default")
      (node (ref "U10") (pin "4") (pinfunction "SS_4") (pintype "passive+no_connect"))
    )
    (net (code "48") (name "unconnected-(U11-SS-Pad4)") (class "Default")
      (node (ref "U11") (pin "4") (pinfunction "SS_4") (pintype "passive+no_connect"))
    )
    (net (code "49") (name "unconnected-(U12-SS-Pad4)") (class "Default")
      (node (ref "U12") (pin "4") (pinfunction "SS_4") (pintype "passive+no_connect"))
    )
  )
)
